# smd.net
KiCad netlist of a schematic drawn in EasyEDA
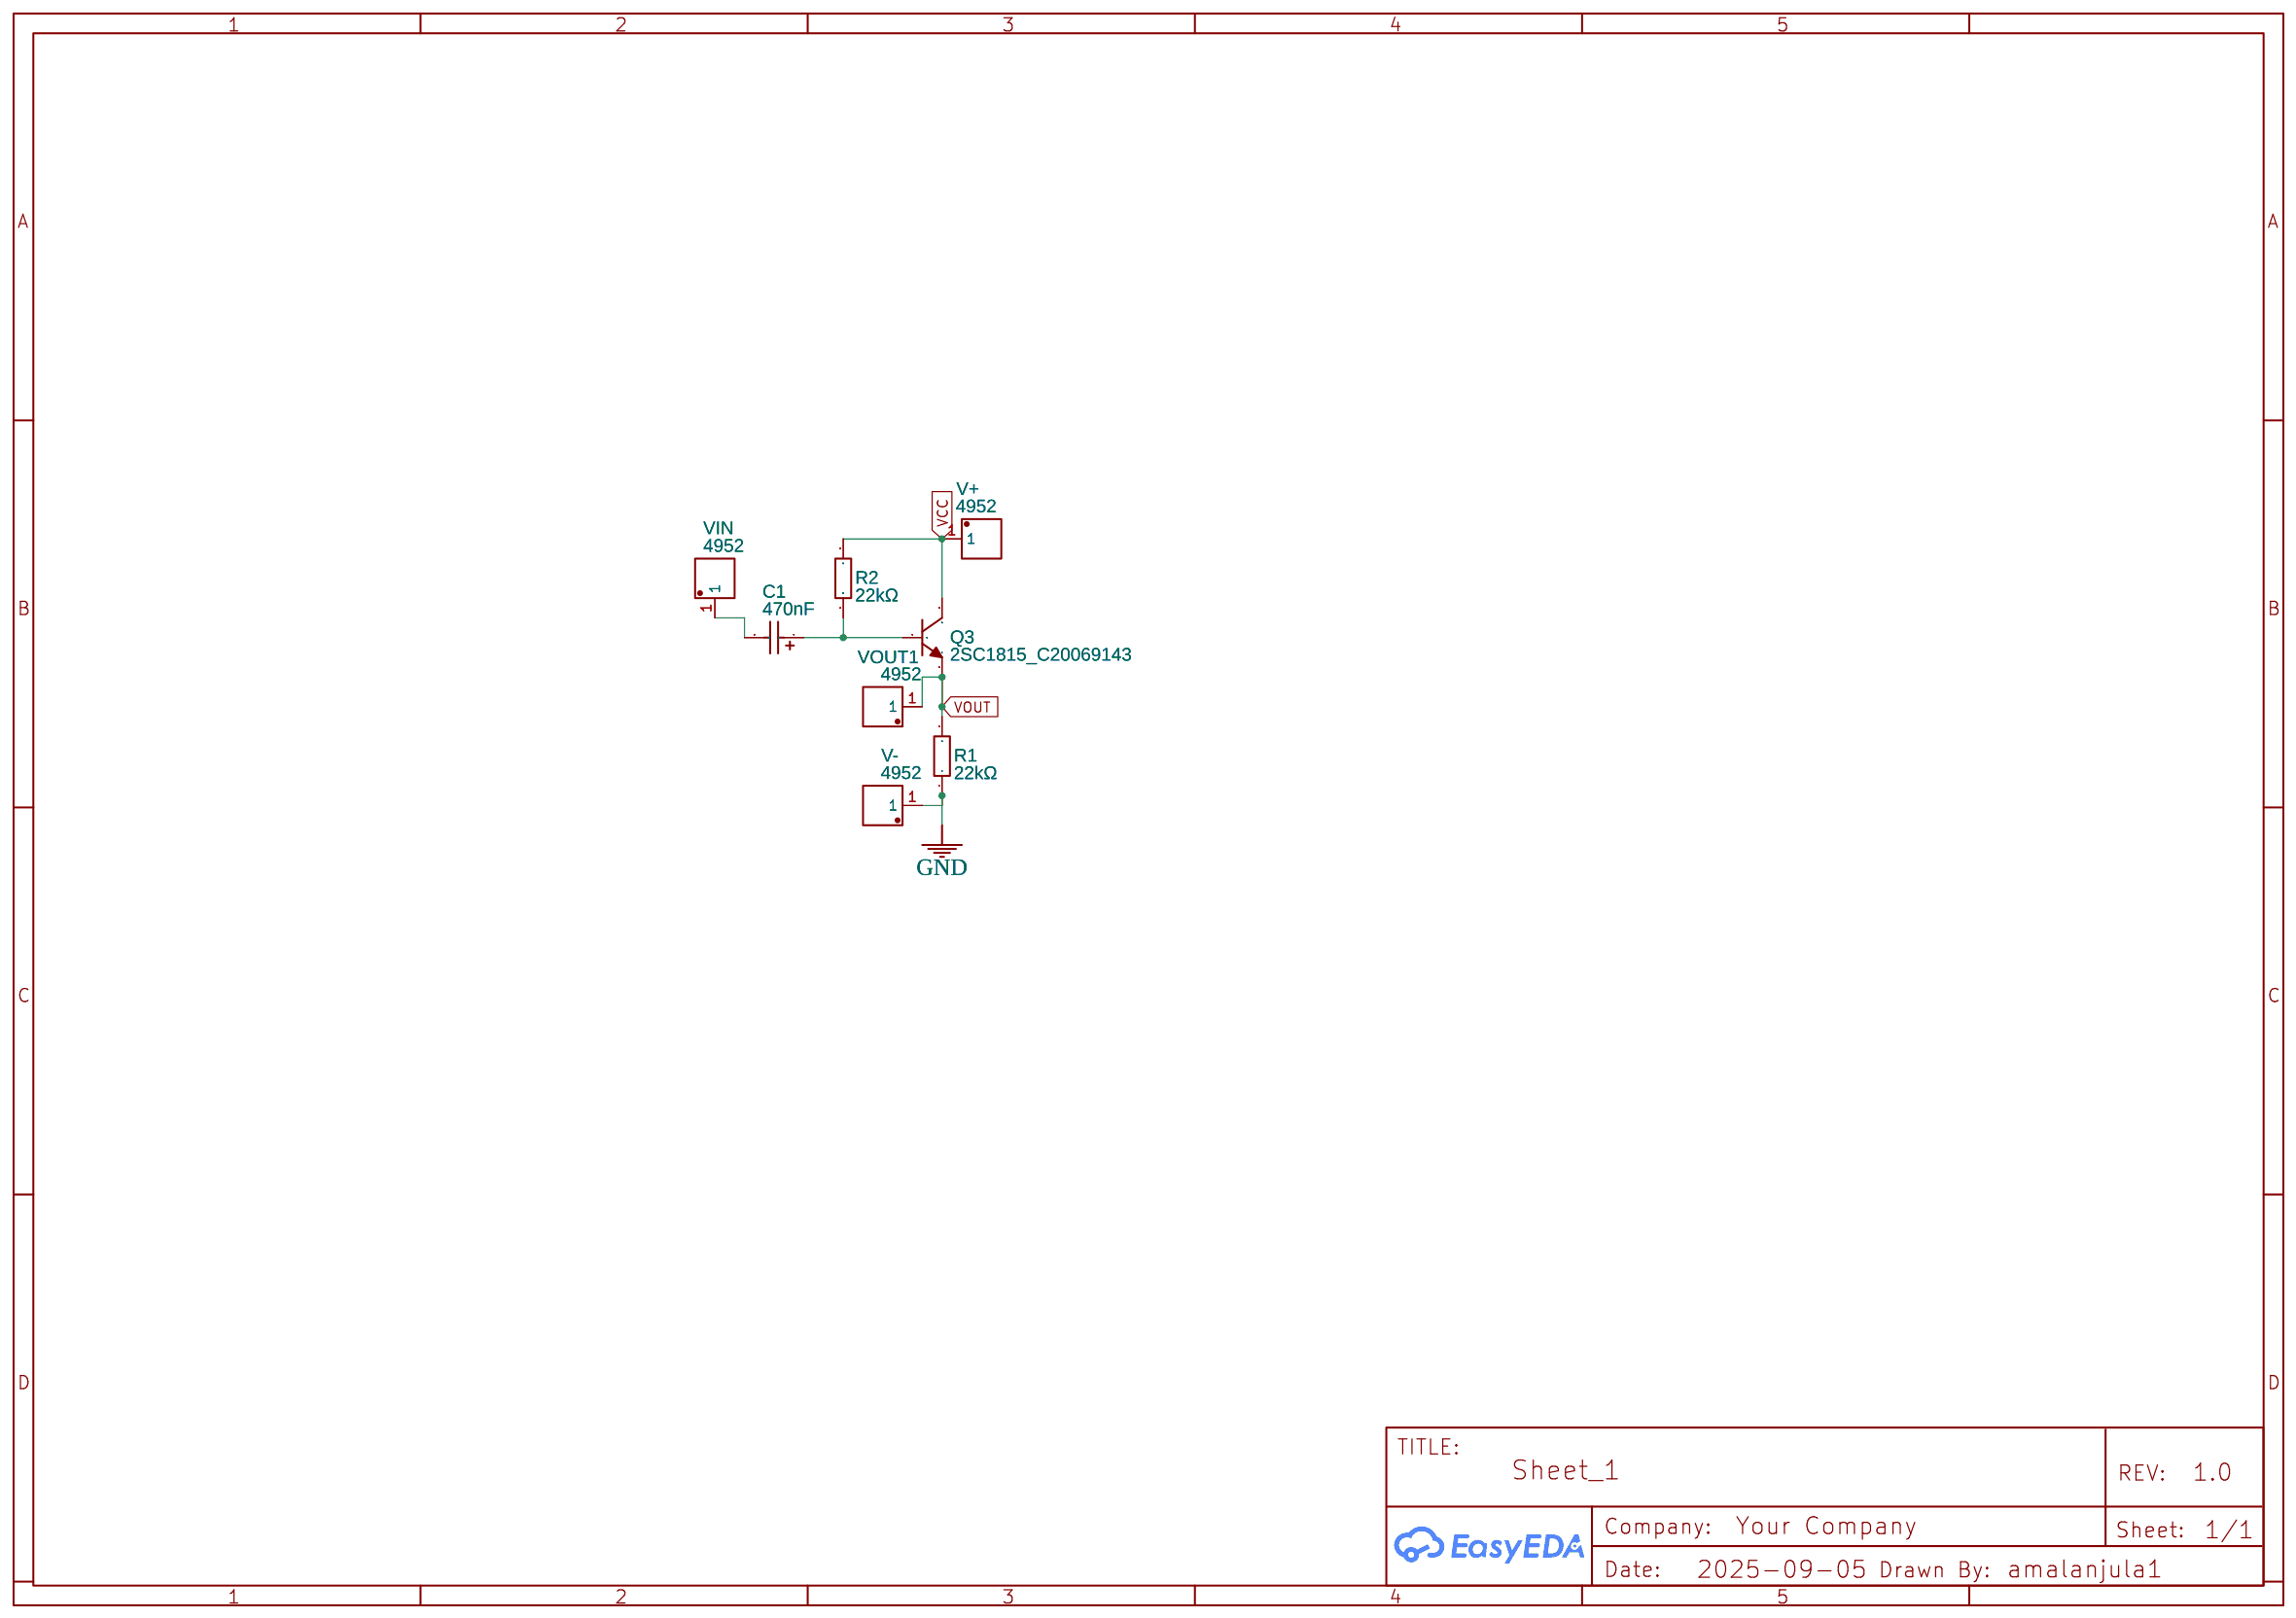
[diagram p0: schematic sheet]

(export (version "E")
  (design (tool "Eeschema 10.0.6"))
  (components
    (comp (ref "C1")
      (value "470nF")
      (fields (field (name "Manufacturer Part") "TAJA474K035RNJ") (field (name "Manufacturer") "Kyocera AVX"))
      (libsource (lib "") (part "TAJA474K035RNJ"))
    )
    (comp (ref "Q3")
      (value "2SC1815_C20069143")
      (fields (field (name "Manufacturer Part") "2SC1815") (field (name "Manufacturer") "R+O(宏嘉诚)"))
      (libsource (lib "") (part "2SC1815_C20069143"))
    )
    (comp (ref "R1")
      (value "22kΩ")
      (fields
        (field (name "Manufacturer Part") "0603WAF2202T5E")
        (field (name "Manufacturer") "UNI-ROYAL(厚声)")
      )
      (libsource (lib "") (part "0603WAF2202T5E"))
    )
    (comp (ref "R2")
      (value "22kΩ")
      (fields
        (field (name "Manufacturer Part") "0603WAF2202T5E")
        (field (name "Manufacturer") "UNI-ROYAL(厚声)")
      )
      (libsource (lib "") (part "0603WAF2202T5E"))
    )
    (comp (ref "V+")
      (value "4952")
      (fields (field (name "Manufacturer") "Keystone"))
      (libsource (lib "") (part "4952_3"))
    )
    (comp (ref "V-")
      (value "4952")
      (fields (field (name "Manufacturer") "Keystone"))
      (libsource (lib "") (part "4952_2"))
    )
    (comp (ref "VIN")
      (value "4952")
      (fields (field (name "Manufacturer") "Keystone"))
      (libsource (lib "") (part "4952"))
    )
    (comp (ref "VOUT1")
      (value "4952")
      (fields (field (name "Manufacturer") "Keystone"))
      (libsource (lib "") (part "4952_1"))
    )
  )
  (nets
    (net (code "1") (name "GND") (class "Default")
      (node (ref "R1") (pin "1") (pinfunction "1_1") (pintype "input"))
      (node (ref "V-") (pin "1") (pinfunction "1_1") (pintype "unspecified"))
    )
    (net (code "2") (name "Net-(C1-Pad2)") (class "Default")
      (node (ref "C1") (pin "2") (pinfunction "2_2") (pintype "input"))
      (node (ref "VIN") (pin "1") (pinfunction "1_1") (pintype "unspecified"))
    )
    (net (code "3") (name "Net-(Q3-B)") (class "Default")
      (node (ref "C1") (pin "1") (pinfunction "1_1") (pintype "input"))
      (node (ref "Q3") (pin "1") (pinfunction "B_1") (pintype "input"))
      (node (ref "R2") (pin "1") (pinfunction "1_1") (pintype "input"))
    )
    (net (code "4") (name "VCC") (class "Default")
      (node (ref "Q3") (pin "3") (pinfunction "C_3") (pintype "input"))
      (node (ref "R2") (pin "2") (pinfunction "2_2") (pintype "input"))
      (node (ref "V+") (pin "1") (pinfunction "1_1") (pintype "unspecified"))
    )
    (net (code "5") (name "VOUT") (class "Default")
      (node (ref "Q3") (pin "2") (pinfunction "E_2") (pintype "input"))
      (node (ref "R1") (pin "2") (pinfunction "2_2") (pintype "input"))
      (node (ref "VOUT1") (pin "1") (pinfunction "1_1") (pintype "unspecified"))
    )
  )
)
